# SparkFunMP3Shield.net
KiCad netlist of a schematic drawn in EAGLE
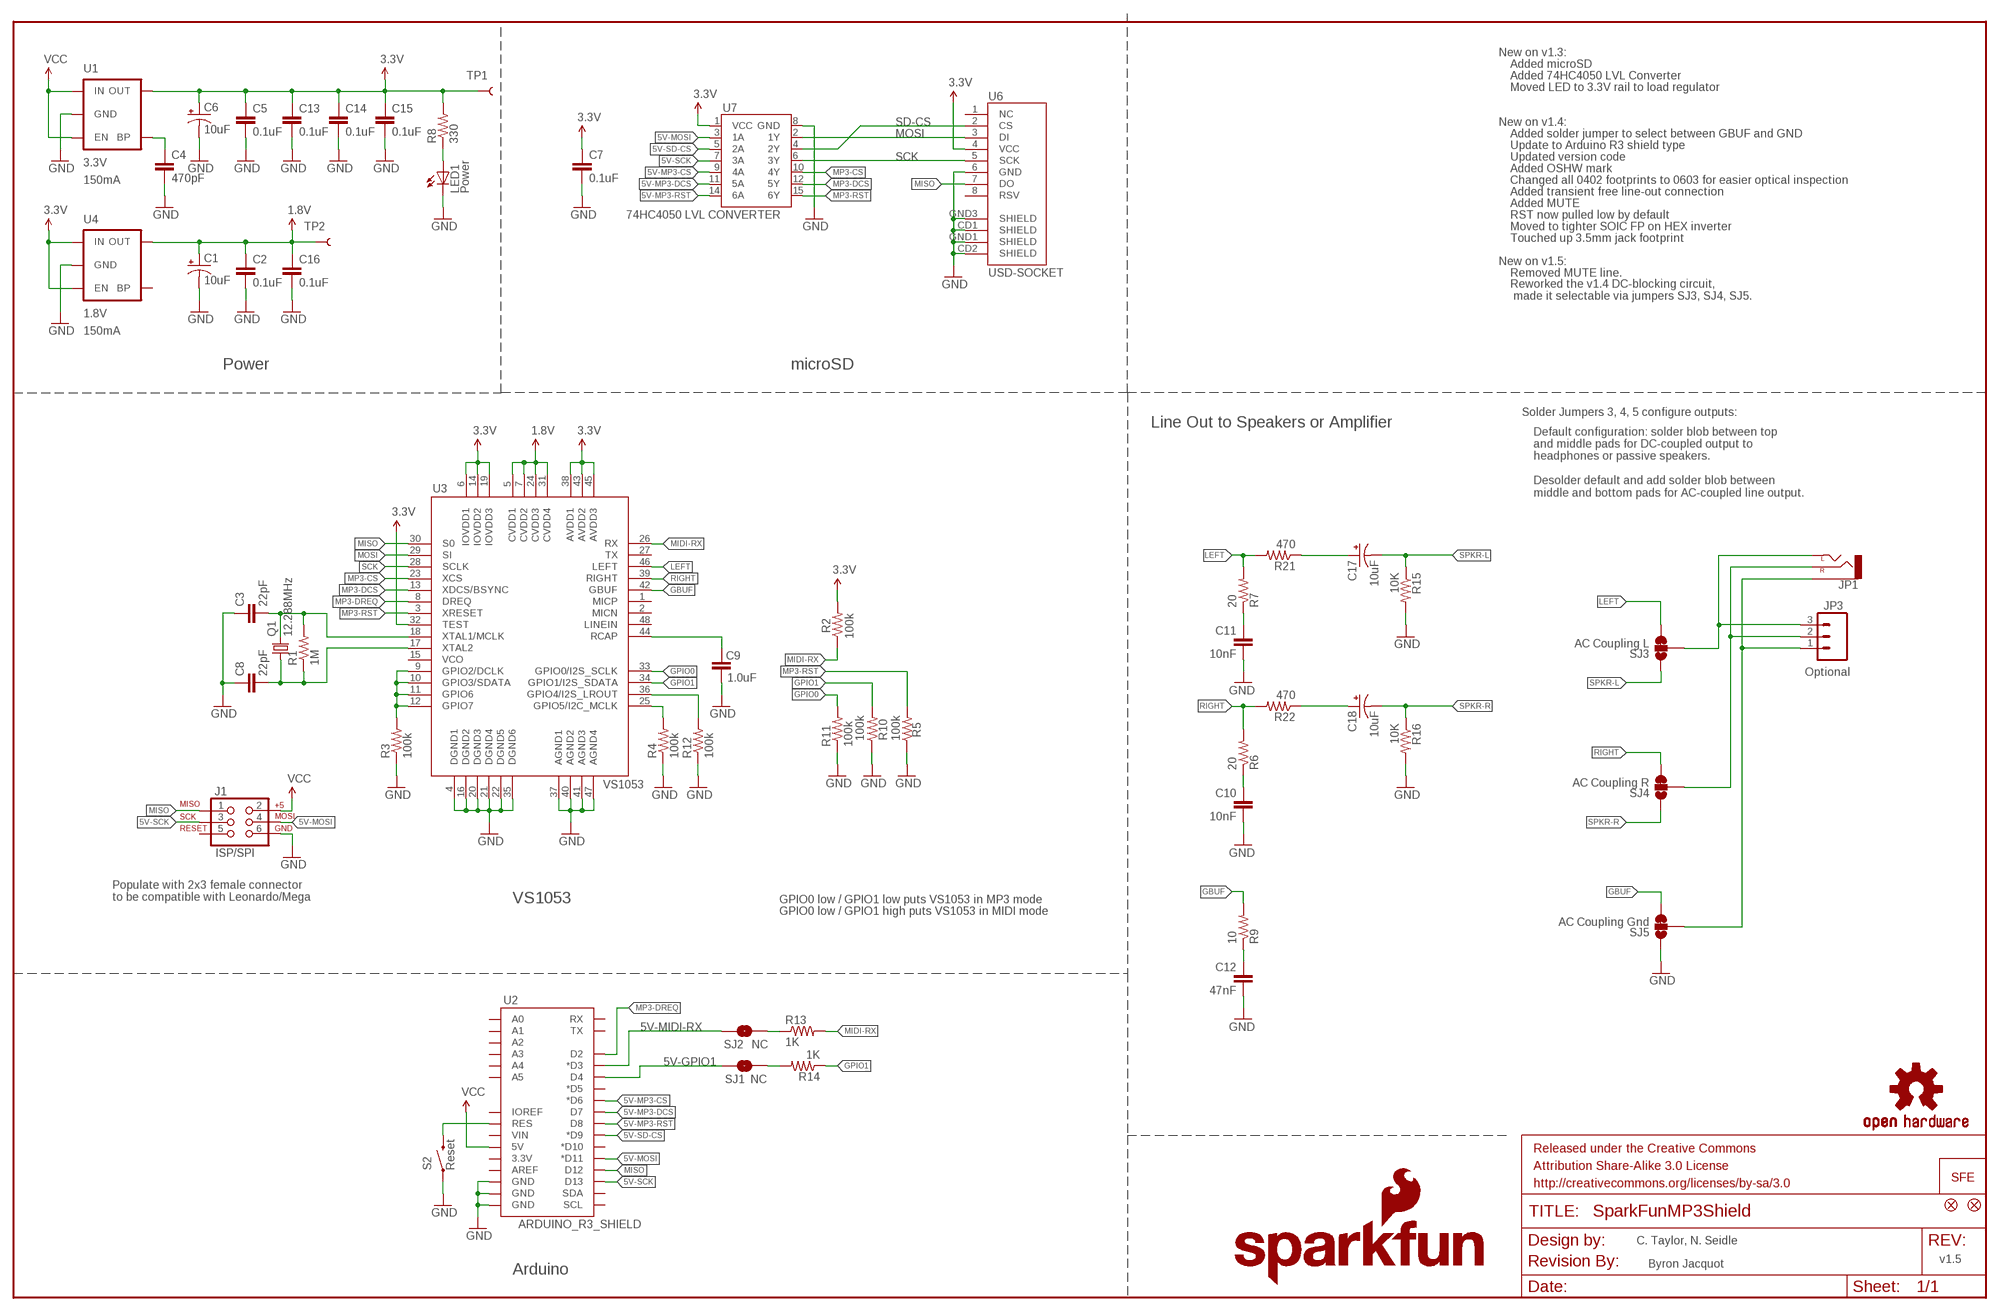
[diagram p0: schematic, sheet 1]

(export (version "E")
  (design (tool "Eeschema 10.0.6"))
  (components
    (comp (ref "C1")
      (value "10uF")
      (footprint "eagle-import:EIA3216")
      (libsource (lib "eagle-import") (part "10UF-16V-10%(TANT)"))
    )
    (comp (ref "C2")
      (value "0.1uF")
      (footprint "eagle-import:0603-CAP")
      (libsource (lib "eagle-import") (part "0.1UF-25V(+80/-20%)(0603)"))
    )
    (comp (ref "C3")
      (value "22pF")
      (footprint "eagle-import:0603-CAP")
      (libsource (lib "eagle-import") (part "22PF-50V-5%(0603)"))
    )
    (comp (ref "C4")
      (value "470pF")
      (footprint "eagle-import:0603-CAP")
      (libsource (lib "eagle-import") (part "470PF-50V-5%(0603)SMD"))
    )
    (comp (ref "C5")
      (value "0.1uF")
      (footprint "eagle-import:0603-CAP")
      (libsource (lib "eagle-import") (part "0.1UF-25V(+80/-20%)(0603)"))
    )
    (comp (ref "C6")
      (value "10uF")
      (footprint "eagle-import:EIA3216")
      (libsource (lib "eagle-import") (part "10UF-16V-10%(TANT)"))
    )
    (comp (ref "C7")
      (value "0.1uF")
      (footprint "eagle-import:0603-CAP")
      (libsource (lib "eagle-import") (part "0.1UF-25V(+80/-20%)(0603)"))
    )
    (comp (ref "C8")
      (value "22pF")
      (footprint "eagle-import:0603-CAP")
      (libsource (lib "eagle-import") (part "22PF-50V-5%(0603)"))
    )
    (comp (ref "C9")
      (value "1.0uF")
      (footprint "eagle-import:0603-CAP")
      (libsource (lib "eagle-import") (part "1.0UF-16V-10%(0603)"))
    )
    (comp (ref "C10")
      (value "10nF")
      (footprint "eagle-import:0603-CAP")
      (libsource (lib "eagle-import") (part "10NF/10000PF-50V-10%(0603)"))
    )
    (comp (ref "C11")
      (value "10nF")
      (footprint "eagle-import:0603-CAP")
      (libsource (lib "eagle-import") (part "10NF/10000PF-50V-10%(0603)"))
    )
    (comp (ref "C12")
      (value "47nF")
      (footprint "eagle-import:0603-CAP")
      (libsource (lib "eagle-import") (part "47NF(0.047UF/47000PF)-25V-5%(0603)SMD"))
    )
    (comp (ref "C13")
      (value "0.1uF")
      (footprint "eagle-import:0603-CAP")
      (libsource (lib "eagle-import") (part "0.1UF-25V(+80/-20%)(0603)"))
    )
    (comp (ref "C14")
      (value "0.1uF")
      (footprint "eagle-import:0603-CAP")
      (libsource (lib "eagle-import") (part "0.1UF-25V(+80/-20%)(0603)"))
    )
    (comp (ref "C15")
      (value "0.1uF")
      (footprint "eagle-import:0603-CAP")
      (libsource (lib "eagle-import") (part "0.1UF-25V(+80/-20%)(0603)"))
    )
    (comp (ref "C16")
      (value "0.1uF")
      (footprint "eagle-import:0603-CAP")
      (libsource (lib "eagle-import") (part "0.1UF-25V(+80/-20%)(0603)"))
    )
    (comp (ref "C17")
      (value "10uF")
      (footprint "eagle-import:EIA3216")
      (libsource (lib "eagle-import") (part "10UF-16V-10%(TANT)"))
    )
    (comp (ref "C18")
      (value "10uF")
      (footprint "eagle-import:EIA3216")
      (libsource (lib "eagle-import") (part "10UF-16V-10%(TANT)"))
    )
    (comp (ref "FRAME1")
      (value "FRAME-LEDGER")
      (footprint "eagle-import:CREATIVE_COMMONS")
      (libsource (lib "eagle-import") (part "FRAME-LEDGER"))
    )
    (comp (ref "J1")
      (value "ISP/SPI")
      (footprint "eagle-import:2X3")
      (libsource (lib "eagle-import") (part "AVR_SPI_PRG_6PTH"))
    )
    (comp (ref "JP1")
      (value "AUDIO-JACKSMD2")
      (footprint "eagle-import:AUDIO-JACK-3.5MM-SMD")
      (libsource (lib "eagle-import") (part "AUDIO-JACKSMD2"))
    )
    (comp (ref "JP3")
      (value "Optional")
      (footprint "eagle-import:1X03")
      (libsource (lib "eagle-import") (part "M03PTH"))
    )
    (comp (ref "LED1")
      (value "Power")
      (footprint "eagle-import:LED-0603")
      (libsource (lib "eagle-import") (part "LED-RED0603"))
    )
    (comp (ref "LOGO1")
      (value "OSHW-LOGOS")
      (footprint "eagle-import:OSHW-LOGO-S")
      (libsource (lib "eagle-import") (part "OSHW-LOGOS"))
    )
    (comp (ref "LOGO2")
      (value "SFE_LOGO_NAME_FLAME.1_INCH")
      (footprint "eagle-import:SFE_LOGO_NAME_FLAME_.1")
      (libsource (lib "eagle-import") (part "SFE_LOGO_NAME_FLAME.1_INCH"))
    )
    (comp (ref "Q1")
      (value "12.288MHz")
      (footprint "eagle-import:CRYSTAL-SMD-5X3")
      (libsource (lib "eagle-import") (part "CRYSTAL5X3"))
    )
    (comp (ref "R1")
      (value "1M")
      (footprint "eagle-import:0603-RES")
      (libsource (lib "eagle-import") (part "1M-1%"))
    )
    (comp (ref "R2")
      (value "100k")
      (footprint "eagle-import:0603-RES")
      (libsource (lib "eagle-import") (part "100KOHM1/10W1%(0603)"))
    )
    (comp (ref "R3")
      (value "100k")
      (footprint "eagle-import:0603-RES")
      (libsource (lib "eagle-import") (part "100KOHM1/10W1%(0603)"))
    )
    (comp (ref "R4")
      (value "100k")
      (footprint "eagle-import:0603-RES")
      (libsource (lib "eagle-import") (part "100KOHM1/10W1%(0603)"))
    )
    (comp (ref "R5")
      (value "100k")
      (footprint "eagle-import:0603-RES")
      (libsource (lib "eagle-import") (part "100KOHM1/10W1%(0603)"))
    )
    (comp (ref "R6")
      (value "20")
      (footprint "eagle-import:0603-RES")
      (libsource (lib "eagle-import") (part "20OHM1/10W1%(0603)SMD"))
    )
    (comp (ref "R7")
      (value "20")
      (footprint "eagle-import:0603-RES")
      (libsource (lib "eagle-import") (part "20OHM1/10W1%(0603)SMD"))
    )
    (comp (ref "R8")
      (value "330")
      (footprint "eagle-import:0603-RES")
      (libsource (lib "eagle-import") (part "330OHM1/10W1%(0603)"))
    )
    (comp (ref "R9")
      (value "10")
      (footprint "eagle-import:0603-RES")
      (libsource (lib "eagle-import") (part "10OHM1/10W5%0603SMD"))
    )
    (comp (ref "R10")
      (value "100k")
      (footprint "eagle-import:0603-RES")
      (libsource (lib "eagle-import") (part "100KOHM1/10W1%(0603)"))
    )
    (comp (ref "R11")
      (value "100k")
      (footprint "eagle-import:0603-RES")
      (libsource (lib "eagle-import") (part "100KOHM1/10W1%(0603)"))
    )
    (comp (ref "R12")
      (value "100k")
      (footprint "eagle-import:0603-RES")
      (libsource (lib "eagle-import") (part "100KOHM1/10W1%(0603)"))
    )
    (comp (ref "R13")
      (value "1K")
      (footprint "eagle-import:0603-RES")
      (libsource (lib "eagle-import") (part "1KOHM1/10W1%(0603)"))
    )
    (comp (ref "R14")
      (value "1K")
      (footprint "eagle-import:0603-RES")
      (libsource (lib "eagle-import") (part "1KOHM1/10W1%(0603)"))
    )
    (comp (ref "R15")
      (value "10K")
      (footprint "eagle-import:0603-RES")
      (libsource (lib "eagle-import") (part "10KOHM1/10W1%(0603)0603"))
    )
    (comp (ref "R16")
      (value "10K")
      (footprint "eagle-import:0603-RES")
      (libsource (lib "eagle-import") (part "10KOHM1/10W1%(0603)0603"))
    )
    (comp (ref "R21")
      (value "470")
      (footprint "eagle-import:0603-RES")
      (libsource (lib "eagle-import") (part "470OHM1/10W1%(0603)"))
    )
    (comp (ref "R22")
      (value "470")
      (footprint "eagle-import:0603-RES")
      (libsource (lib "eagle-import") (part "470OHM1/10W1%(0603)"))
    )
    (comp (ref "S2")
      (value "Reset")
      (footprint "eagle-import:TACTILE_SWITCH_SMD")
      (libsource (lib "eagle-import") (part "SWITCH-MOMENTARY-2SMD"))
    )
    (comp (ref "SJ1")
      (value "NC")
      (footprint "eagle-import:SJ_2S-TRACE")
      (libsource (lib "eagle-import") (part "SOLDERJUMPERTRACE"))
    )
    (comp (ref "SJ2")
      (value "NC")
      (footprint "eagle-import:SJ_2S-TRACE")
      (libsource (lib "eagle-import") (part "SOLDERJUMPERTRACE"))
    )
    (comp (ref "SJ3")
      (value "AC Coupling L")
      (footprint "eagle-import:SMT-JUMPER_3_1-NC_TRACE_SILK")
      (libsource (lib "eagle-import") (part "JUMPER-SMT_3_1-NC_TRACE_SILK"))
    )
    (comp (ref "SJ4")
      (value "AC Coupling R")
      (footprint "eagle-import:SMT-JUMPER_3_1-NC_TRACE_SILK")
      (libsource (lib "eagle-import") (part "JUMPER-SMT_3_1-NC_TRACE_SILK"))
    )
    (comp (ref "SJ5")
      (value "AC Coupling Gnd")
      (footprint "eagle-import:SMT-JUMPER_3_1-NC_TRACE_SILK")
      (libsource (lib "eagle-import") (part "JUMPER-SMT_3_1-NC_TRACE_SILK"))
    )
    (comp (ref "TP1")
      (value "TEST-POINT3X5")
      (footprint "eagle-import:PAD.03X.05")
      (libsource (lib "eagle-import") (part "TEST-POINT3X5"))
    )
    (comp (ref "TP2")
      (value "TEST-POINT3X5")
      (footprint "eagle-import:PAD.03X.05")
      (libsource (lib "eagle-import") (part "TEST-POINT3X5"))
    )
    (comp (ref "U$1")
      (value "REVISION")
      (footprint "eagle-import:REVISION")
      (libsource (lib "eagle-import") (part "REVISION"))
    )
    (comp (ref "U$4")
      (value "FIDUCIAL1X2")
      (footprint "eagle-import:FIDUCIAL-1X2")
      (libsource (lib "eagle-import") (part "FIDUCIAL1X2"))
    )
    (comp (ref "U$5")
      (value "FIDUCIAL1X2")
      (footprint "eagle-import:FIDUCIAL-1X2")
      (libsource (lib "eagle-import") (part "FIDUCIAL1X2"))
    )
    (comp (ref "U$8")
      (value "LOGO-SFENEW")
      (footprint "eagle-import:SFE-NEW-WEBLOGO")
      (libsource (lib "eagle-import") (part "LOGO-SFENEW"))
    )
    (comp (ref "U1")
      (value "3.3V")
      (footprint "eagle-import:SOT23-5")
      (libsource (lib "eagle-import") (part "V_REG_MIC52053.3V"))
    )
    (comp (ref "U2")
      (value "ARDUINO_R3_SHIELD")
      (footprint "eagle-import:UNO_R3_SHIELD")
      (libsource (lib "eagle-import") (part "ARDUINO_R3_SHIELD"))
    )
    (comp (ref "U3")
      (value "VS1053")
      (footprint "eagle-import:LQFP-48")
      (libsource (lib "eagle-import") (part "VS1033/1053SMD"))
    )
    (comp (ref "U4")
      (value "1.8V")
      (footprint "eagle-import:SC70")
      (libsource (lib "eagle-import") (part "V_REG_SP62141.8V"))
    )
    (comp (ref "U6")
      (value "USD-SOCKET")
      (footprint "eagle-import:MICRO-SD-SOCKET-PP")
      (libsource (lib "eagle-import") (part "USD-SOCKETNEW"))
    )
    (comp (ref "U7")
      (value "74HC4050 LVL CONVERTER")
      (footprint "eagle-import:SO016")
      (libsource (lib "eagle-import") (part "HEX_CONVERTER"))
    )
  )
  (nets
    (net (code "1") (name "/5V-GPIO1") (class "Default")
      (node (ref "SJ1") (pin "2") (pinfunction "2_2") (pintype "passive"))
      (node (ref "U2") (pin "D4") (pinfunction "D4_D4") (pintype "bidirectional"))
    )
    (net (code "2") (name "/5V-MIDI-RX") (class "Default")
      (node (ref "SJ2") (pin "1") (pinfunction "1_1") (pintype "passive"))
      (node (ref "U2") (pin "D3") (pinfunction "*D3_D3") (pintype "bidirectional"))
    )
    (net (code "3") (name "/SD-CS") (class "Default")
      (node (ref "U6") (pin "2") (pinfunction "CS_2") (pintype "bidirectional"))
      (node (ref "U7") (pin "4") (pinfunction "2Y_4") (pintype "bidirectional"))
    )
    (net (code "4") (name "1.8V") (class "Default")
      (node (ref "C1") (pin "A") (pinfunction "+_A") (pintype "passive"))
      (node (ref "C16") (pin "1") (pinfunction "1_1") (pintype "passive"))
      (node (ref "C2") (pin "1") (pinfunction "1_1") (pintype "passive"))
      (node (ref "TP2") (pin "P$1") (pinfunction "1_P$1") (pintype "bidirectional"))
      (node (ref "U3") (pin "24") (pinfunction "CVDD3_24") (pintype "bidirectional"))
      (node (ref "U3") (pin "31") (pinfunction "CVDD4_31") (pintype "bidirectional"))
      (node (ref "U3") (pin "5") (pinfunction "CVDD1_5") (pintype "bidirectional"))
      (node (ref "U3") (pin "7") (pinfunction "CVDD2_7") (pintype "bidirectional"))
      (node (ref "U4") (pin "5") (pinfunction "OUT_5") (pintype "passive"))
    )
    (net (code "5") (name "3.3V") (class "Default")
      (node (ref "C13") (pin "1") (pinfunction "1_1") (pintype "passive"))
      (node (ref "C14") (pin "1") (pinfunction "1_1") (pintype "passive"))
      (node (ref "C15") (pin "1") (pinfunction "1_1") (pintype "passive"))
      (node (ref "C5") (pin "1") (pinfunction "1_1") (pintype "passive"))
      (node (ref "C6") (pin "A") (pinfunction "+_A") (pintype "passive"))
      (node (ref "C7") (pin "1") (pinfunction "1_1") (pintype "passive"))
      (node (ref "R2") (pin "2") (pinfunction "2_2") (pintype "passive"))
      (node (ref "R8") (pin "2") (pinfunction "2_2") (pintype "passive"))
      (node (ref "TP1") (pin "P$1") (pinfunction "1_P$1") (pintype "bidirectional"))
      (node (ref "U1") (pin "5") (pinfunction "OUT_5") (pintype "passive"))
      (node (ref "U3") (pin "14") (pinfunction "IOVDD2_14") (pintype "bidirectional"))
      (node (ref "U3") (pin "19") (pinfunction "IOVDD3_19") (pintype "bidirectional"))
      (node (ref "U3") (pin "32") (pinfunction "TEST_32") (pintype "bidirectional"))
      (node (ref "U3") (pin "38") (pinfunction "AVDD1_38") (pintype "bidirectional"))
      (node (ref "U3") (pin "43") (pinfunction "AVDD2_43") (pintype "bidirectional"))
      (node (ref "U3") (pin "45") (pinfunction "AVDD3_45") (pintype "bidirectional"))
      (node (ref "U3") (pin "6") (pinfunction "IOVDD1_6") (pintype "bidirectional"))
      (node (ref "U4") (pin "1") (pinfunction "IN_1") (pintype "input"))
      (node (ref "U4") (pin "3") (pinfunction "EN_3") (pintype "input"))
      (node (ref "U6") (pin "4") (pinfunction "VCC_4") (pintype "bidirectional"))
      (node (ref "U7") (pin "1") (pinfunction "VCC_1") (pintype "bidirectional"))
    )
    (net (code "6") (name "5V-MOSI") (class "Default")
      (node (ref "J1") (pin "4") (pinfunction "4_4") (pintype "passive"))
      (node (ref "U2") (pin "D11") (pinfunction "*D11_D11") (pintype "bidirectional"))
      (node (ref "U7") (pin "3") (pinfunction "1A_3") (pintype "bidirectional"))
    )
    (net (code "7") (name "5V-MP3-CS") (class "Default")
      (node (ref "U2") (pin "D6") (pinfunction "*D6_D6") (pintype "bidirectional"))
      (node (ref "U7") (pin "9") (pinfunction "4A_9") (pintype "bidirectional"))
    )
    (net (code "8") (name "5V-MP3-DCS") (class "Default")
      (node (ref "U2") (pin "D7") (pinfunction "D7_D7") (pintype "bidirectional"))
      (node (ref "U7") (pin "11") (pinfunction "5A_11") (pintype "bidirectional"))
    )
    (net (code "9") (name "5V-MP3-RST") (class "Default")
      (node (ref "U2") (pin "D8") (pinfunction "D8_D8") (pintype "bidirectional"))
      (node (ref "U7") (pin "14") (pinfunction "6A_14") (pintype "bidirectional"))
    )
    (net (code "10") (name "5V-SCK") (class "Default")
      (node (ref "J1") (pin "3") (pinfunction "3_3") (pintype "passive"))
      (node (ref "U2") (pin "D13") (pinfunction "D13_D13") (pintype "bidirectional"))
      (node (ref "U7") (pin "7") (pinfunction "3A_7") (pintype "bidirectional"))
    )
    (net (code "11") (name "5V-SD-CS") (class "Default")
      (node (ref "U2") (pin "D9") (pinfunction "*D9_D9") (pintype "bidirectional"))
      (node (ref "U7") (pin "5") (pinfunction "2A_5") (pintype "bidirectional"))
    )
    (net (code "12") (name "GBUF") (class "Default")
      (node (ref "R9") (pin "2") (pinfunction "2_2") (pintype "passive"))
      (node (ref "SJ5") (pin "3") (pinfunction "3_3") (pintype "passive"))
      (node (ref "U3") (pin "42") (pinfunction "GBUF_42") (pintype "bidirectional"))
    )
    (net (code "13") (name "GND") (class "Default")
      (node (ref "C1") (pin "C") (pinfunction "-_C") (pintype "passive"))
      (node (ref "C10") (pin "2") (pinfunction "2_2") (pintype "passive"))
      (node (ref "C11") (pin "2") (pinfunction "2_2") (pintype "passive"))
      (node (ref "C12") (pin "2") (pinfunction "2_2") (pintype "passive"))
      (node (ref "C13") (pin "2") (pinfunction "2_2") (pintype "passive"))
      (node (ref "C14") (pin "2") (pinfunction "2_2") (pintype "passive"))
      (node (ref "C15") (pin "2") (pinfunction "2_2") (pintype "passive"))
      (node (ref "C16") (pin "2") (pinfunction "2_2") (pintype "passive"))
      (node (ref "C2") (pin "2") (pinfunction "2_2") (pintype "passive"))
      (node (ref "C3") (pin "1") (pinfunction "1_1") (pintype "passive"))
      (node (ref "C4") (pin "2") (pinfunction "2_2") (pintype "passive"))
      (node (ref "C5") (pin "2") (pinfunction "2_2") (pintype "passive"))
      (node (ref "C6") (pin "C") (pinfunction "-_C") (pintype "passive"))
      (node (ref "C7") (pin "2") (pinfunction "2_2") (pintype "passive"))
      (node (ref "C8") (pin "1") (pinfunction "1_1") (pintype "passive"))
      (node (ref "C9") (pin "1") (pinfunction "1_1") (pintype "passive"))
      (node (ref "J1") (pin "6") (pinfunction "6_6") (pintype "passive"))
      (node (ref "LED1") (pin "C") (pinfunction "C_C") (pintype "passive"))
      (node (ref "R10") (pin "1") (pinfunction "1_1") (pintype "passive"))
      (node (ref "R11") (pin "1") (pinfunction "1_1") (pintype "passive"))
      (node (ref "R12") (pin "1") (pinfunction "1_1") (pintype "passive"))
      (node (ref "R15") (pin "2") (pinfunction "2_2") (pintype "passive"))
      (node (ref "R16") (pin "2") (pinfunction "2_2") (pintype "passive"))
      (node (ref "R3") (pin "1") (pinfunction "1_1") (pintype "passive"))
      (node (ref "R4") (pin "1") (pinfunction "1_1") (pintype "passive"))
      (node (ref "R5") (pin "1") (pinfunction "1_1") (pintype "passive"))
      (node (ref "S2") (pin "1") (pinfunction "1_1") (pintype "passive"))
      (node (ref "SJ5") (pin "1") (pinfunction "1_1") (pintype "passive"))
      (node (ref "U1") (pin "2") (pinfunction "GND_2") (pintype "input"))
      (node (ref "U2") (pin "GND@0") (pinfunction "GND_GND@0") (pintype "bidirectional"))
      (node (ref "U2") (pin "GND@1") (pinfunction "GND_GND@1") (pintype "bidirectional"))
      (node (ref "U2") (pin "GND@2") (pinfunction "GND_GND@2") (pintype "bidirectional"))
      (node (ref "U3") (pin "16") (pinfunction "DGND2_16") (pintype "bidirectional"))
      (node (ref "U3") (pin "20") (pinfunction "DGND3_20") (pintype "bidirectional"))
      (node (ref "U3") (pin "21") (pinfunction "DGND4_21") (pintype "bidirectional"))
      (node (ref "U3") (pin "22") (pinfunction "DGND5_22") (pintype "bidirectional"))
      (node (ref "U3") (pin "35") (pinfunction "DGND6_35") (pintype "bidirectional"))
      (node (ref "U3") (pin "37") (pinfunction "AGND1_37") (pintype "bidirectional"))
      (node (ref "U3") (pin "4") (pinfunction "DGND1_4") (pintype "bidirectional"))
      (node (ref "U3") (pin "40") (pinfunction "AGND2_40") (pintype "bidirectional"))
      (node (ref "U3") (pin "41") (pinfunction "AGND3_41") (pintype "bidirectional"))
      (node (ref "U3") (pin "47") (pinfunction "AGND4_47") (pintype "bidirectional"))
      (node (ref "U4") (pin "2") (pinfunction "GND_2") (pintype "input"))
      (node (ref "U6") (pin "6") (pinfunction "GND_6") (pintype "bidirectional"))
      (node (ref "U6") (pin "CD1") (pinfunction "SHIELD_CD1") (pintype "bidirectional"))
      (node (ref "U6") (pin "CD2") (pinfunction "SHIELD_CD2") (pintype "bidirectional"))
      (node (ref "U6") (pin "GND1") (pinfunction "SHIELD_GND1") (pintype "bidirectional"))
      (node (ref "U6") (pin "GND3") (pinfunction "SHIELD_GND3") (pintype "bidirectional"))
      (node (ref "U7") (pin "8") (pinfunction "GND_8") (pintype "bidirectional"))
    )
    (net (code "14") (name "GPIO0") (class "Default")
      (node (ref "R11") (pin "2") (pinfunction "2_2") (pintype "passive"))
      (node (ref "U3") (pin "33") (pinfunction "GPIO0/I2S_SCLK_33") (pintype "bidirectional"))
    )
    (net (code "15") (name "GPIO1") (class "Default")
      (node (ref "R10") (pin "2") (pinfunction "2_2") (pintype "passive"))
      (node (ref "R14") (pin "1") (pinfunction "1_1") (pintype "passive"))
      (node (ref "U3") (pin "34") (pinfunction "GPIO1/I2S_SDATA_34") (pintype "bidirectional"))
    )
    (net (code "16") (name "LEFT") (class "Default")
      (node (ref "R21") (pin "2") (pinfunction "2_2") (pintype "passive"))
      (node (ref "R7") (pin "2") (pinfunction "2_2") (pintype "passive"))
      (node (ref "SJ3") (pin "3") (pinfunction "3_3") (pintype "passive"))
      (node (ref "U3") (pin "46") (pinfunction "LEFT_46") (pintype "bidirectional"))
    )
    (net (code "17") (name "MIDI-RX") (class "Default")
      (node (ref "R13") (pin "2") (pinfunction "2_2") (pintype "passive"))
      (node (ref "R2") (pin "1") (pinfunction "1_1") (pintype "passive"))
      (node (ref "U3") (pin "26") (pinfunction "RX_26") (pintype "bidirectional"))
    )
    (net (code "18") (name "MISO") (class "Default")
      (node (ref "J1") (pin "1") (pinfunction "1_1") (pintype "passive"))
      (node (ref "U2") (pin "D12") (pinfunction "D12_D12") (pintype "bidirectional"))
      (node (ref "U3") (pin "30") (pinfunction "S0_30") (pintype "bidirectional"))
      (node (ref "U6") (pin "7") (pinfunction "DO_7") (pintype "bidirectional"))
    )
    (net (code "19") (name "MOSI") (class "Default")
      (node (ref "U3") (pin "29") (pinfunction "SI_29") (pintype "bidirectional"))
      (node (ref "U6") (pin "3") (pinfunction "DI_3") (pintype "bidirectional"))
      (node (ref "U7") (pin "2") (pinfunction "1Y_2") (pintype "bidirectional"))
    )
    (net (code "20") (name "MP3-CS") (class "Default")
      (node (ref "U3") (pin "23") (pinfunction "XCS_23") (pintype "bidirectional"))
      (node (ref "U7") (pin "10") (pinfunction "4Y_10") (pintype "bidirectional"))
    )
    (net (code "21") (name "MP3-DCS") (class "Default")
      (node (ref "U3") (pin "13") (pinfunction "XDCS/BSYNC_13") (pintype "bidirectional"))
      (node (ref "U7") (pin "12") (pinfunction "5Y_12") (pintype "bidirectional"))
    )
    (net (code "22") (name "MP3-DREQ") (class "Default")
      (node (ref "U2") (pin "D2") (pinfunction "D2_D2") (pintype "bidirectional"))
      (node (ref "U3") (pin "8") (pinfunction "DREQ_8") (pintype "bidirectional"))
    )
    (net (code "23") (name "MP3-RST") (class "Default")
      (node (ref "R5") (pin "2") (pinfunction "2_2") (pintype "passive"))
      (node (ref "U3") (pin "3") (pinfunction "XRESET_3") (pintype "bidirectional"))
      (node (ref "U7") (pin "15") (pinfunction "6Y_15") (pintype "bidirectional"))
    )
    (net (code "24") (name "Net-(C10-Pad1)") (class "Default")
      (node (ref "C10") (pin "1") (pinfunction "1_1") (pintype "passive"))
      (node (ref "R6") (pin "1") (pinfunction "1_1") (pintype "passive"))
    )
    (net (code "25") (name "Net-(C11-Pad1)") (class "Default")
      (node (ref "C11") (pin "1") (pinfunction "1_1") (pintype "passive"))
      (node (ref "R7") (pin "1") (pinfunction "1_1") (pintype "passive"))
    )
    (net (code "26") (name "Net-(C12-Pad1)") (class "Default")
      (node (ref "C12") (pin "1") (pinfunction "1_1") (pintype "passive"))
      (node (ref "R9") (pin "1") (pinfunction "1_1") (pintype "passive"))
    )
    (net (code "27") (name "Net-(C17-+)") (class "Default")
      (node (ref "C17") (pin "A") (pinfunction "+_A") (pintype "passive"))
      (node (ref "R21") (pin "1") (pinfunction "1_1") (pintype "passive"))
    )
    (net (code "28") (name "Net-(C18-+)") (class "Default")
      (node (ref "C18") (pin "A") (pinfunction "+_A") (pintype "passive"))
      (node (ref "R22") (pin "1") (pinfunction "1_1") (pintype "passive"))
    )
    (net (code "29") (name "Net-(JP1-LEFT)") (class "Default")
      (node (ref "JP1") (pin "TIP") (pinfunction "LEFT_TIP") (pintype "bidirectional"))
      (node (ref "JP3") (pin "3") (pinfunction "3_3") (pintype "passive"))
      (node (ref "SJ3") (pin "2") (pinfunction "2_2") (pintype "passive"))
    )
    (net (code "30") (name "Net-(JP1-PadSLEEVE)") (class "Default")
      (node (ref "JP1") (pin "SLEEVE") (pinfunction "SLEEVE_SLEEVE") (pintype "bidirectional"))
      (node (ref "JP3") (pin "1") (pinfunction "1_1") (pintype "passive"))
      (node (ref "SJ5") (pin "2") (pinfunction "2_2") (pintype "passive"))
    )
    (net (code "31") (name "Net-(JP1-RIGHT)") (class "Default")
      (node (ref "JP1") (pin "RING") (pinfunction "RIGHT_RING") (pintype "bidirectional"))
      (node (ref "JP3") (pin "2") (pinfunction "2_2") (pintype "passive"))
      (node (ref "SJ4") (pin "2") (pinfunction "2_2") (pintype "passive"))
    )
    (net (code "32") (name "Net-(LED1-PadA)") (class "Default")
      (node (ref "LED1") (pin "A") (pinfunction "A_A") (pintype "passive"))
      (node (ref "R8") (pin "1") (pinfunction "1_1") (pintype "passive"))
    )
    (net (code "33") (name "Net-(Q1-2)") (class "Default")
      (node (ref "C3") (pin "2") (pinfunction "2_2") (pintype "passive"))
      (node (ref "Q1") (pin "3") (pinfunction "2_3") (pintype "passive"))
      (node (ref "R1") (pin "2") (pinfunction "2_2") (pintype "passive"))
      (node (ref "U3") (pin "18") (pinfunction "XTAL1/MCLK_18") (pintype "bidirectional"))
    )
    (net (code "34") (name "Net-(R13-Pad1)") (class "Default")
      (node (ref "R13") (pin "1") (pinfunction "1_1") (pintype "passive"))
      (node (ref "SJ2") (pin "2") (pinfunction "2_2") (pintype "passive"))
    )
    (net (code "35") (name "Net-(R14-Pad2)") (class "Default")
      (node (ref "R14") (pin "2") (pinfunction "2_2") (pintype "passive"))
      (node (ref "SJ1") (pin "1") (pinfunction "1_1") (pintype "passive"))
    )
    (net (code "36") (name "Net-(S2-2)") (class "Default")
      (node (ref "S2") (pin "3") (pinfunction "2_3") (pintype "passive"))
      (node (ref "U2") (pin "RES") (pinfunction "RES_RES") (pintype "bidirectional"))
    )
    (net (code "37") (name "Net-(U1-BP)") (class "Default")
      (node (ref "C4") (pin "1") (pinfunction "1_1") (pintype "passive"))
      (node (ref "U1") (pin "4") (pinfunction "BP_4") (pintype "input"))
    )
    (net (code "38") (name "Net-(U3-GPIO2{slash}DCLK)") (class "Default")
      (node (ref "R3") (pin "2") (pinfunction "2_2") (pintype "passive"))
      (node (ref "U3") (pin "10") (pinfunction "GPIO3/SDATA_10") (pintype "bidirectional"))
      (node (ref "U3") (pin "11") (pinfunction "GPIO6_11") (pintype "bidirectional"))
      (node (ref "U3") (pin "12") (pinfunction "GPIO7_12") (pintype "bidirectional"))
      (node (ref "U3") (pin "9") (pinfunction "GPIO2/DCLK_9") (pintype "bidirectional"))
    )
    (net (code "39") (name "Net-(U3-GPIO4{slash}I2S_LROUT)") (class "Default")
      (node (ref "R12") (pin "2") (pinfunction "2_2") (pintype "passive"))
      (node (ref "U3") (pin "36") (pinfunction "GPIO4/I2S_LROUT_36") (pintype "bidirectional"))
    )
    (net (code "40") (name "Net-(U3-GPIO5{slash}I2C_MCLK)") (class "Default")
      (node (ref "R4") (pin "2") (pinfunction "2_2") (pintype "passive"))
      (node (ref "U3") (pin "25") (pinfunction "GPIO5/I2C_MCLK_25") (pintype "bidirectional"))
    )
    (net (code "41") (name "Net-(U3-RCAP)") (class "Default")
      (node (ref "C9") (pin "2") (pinfunction "2_2") (pintype "passive"))
      (node (ref "U3") (pin "44") (pinfunction "RCAP_44") (pintype "bidirectional"))
    )
    (net (code "42") (name "Net-(U3-XTAL2)") (class "Default")
      (node (ref "C8") (pin "2") (pinfunction "2_2") (pintype "passive"))
      (node (ref "Q1") (pin "1") (pinfunction "1_1") (pintype "passive"))
      (node (ref "R1") (pin "1") (pinfunction "1_1") (pintype "passive"))
      (node (ref "U3") (pin "17") (pinfunction "XTAL2_17") (pintype "bidirectional"))
    )
    (net (code "43") (name "RIGHT") (class "Default")
      (node (ref "R22") (pin "2") (pinfunction "2_2") (pintype "passive"))
      (node (ref "R6") (pin "2") (pinfunction "2_2") (pintype "passive"))
      (node (ref "SJ4") (pin "3") (pinfunction "3_3") (pintype "passive"))
      (node (ref "U3") (pin "39") (pinfunction "RIGHT_39") (pintype "bidirectional"))
    )
    (net (code "44") (name "SCK") (class "Default")
      (node (ref "U3") (pin "28") (pinfunction "SCLK_28") (pintype "bidirectional"))
      (node (ref "U6") (pin "5") (pinfunction "SCK_5") (pintype "bidirectional"))
      (node (ref "U7") (pin "6") (pinfunction "3Y_6") (pintype "bidirectional"))
    )
    (net (code "45") (name "SPKR-L") (class "Default")
      (node (ref "C17") (pin "C") (pinfunction "-_C") (pintype "passive"))
      (node (ref "R15") (pin "1") (pinfunction "1_1") (pintype "passive"))
      (node (ref "SJ3") (pin "1") (pinfunction "1_1") (pintype "passive"))
    )
    (net (code "46") (name "SPKR-R") (class "Default")
      (node (ref "C18") (pin "C") (pinfunction "-_C") (pintype "passive"))
      (node (ref "R16") (pin "1") (pinfunction "1_1") (pintype "passive"))
      (node (ref "SJ4") (pin "1") (pinfunction "1_1") (pintype "passive"))
    )
    (net (code "47") (name "VCC") (class "Default")
      (node (ref "J1") (pin "2") (pinfunction "2_2") (pintype "passive"))
      (node (ref "U1") (pin "1") (pinfunction "IN_1") (pintype "input"))
      (node (ref "U1") (pin "3") (pinfunction "EN_3") (pintype "input"))
      (node (ref "U2") (pin "5V") (pinfunction "5V_5V") (pintype "bidirectional"))
    )
    (net (code "48") (name "unconnected-(J1-Pad5)") (class "Default")
      (node (ref "J1") (pin "5") (pinfunction "5_5") (pintype "passive"))
    )
    (net (code "49") (name "unconnected-(U2-*D5-PadD5)") (class "Default")
      (node (ref "U2") (pin "D5") (pinfunction "*D5_D5") (pintype "bidirectional"))
    )
    (net (code "50") (name "unconnected-(U2-*D10-PadD10)") (class "Default")
      (node (ref "U2") (pin "D10") (pinfunction "*D10_D10") (pintype "bidirectional"))
    )
    (net (code "51") (name "unconnected-(U2-Pad3.3V)") (class "Default")
      (node (ref "U2") (pin "3.3V") (pinfunction "3.3V_3.3V") (pintype "bidirectional"))
    )
    (net (code "52") (name "unconnected-(U2-PadA0)") (class "Default")
      (node (ref "U2") (pin "A0") (pinfunction "A0_A0") (pintype "bidirectional"))
    )
    (net (code "53") (name "unconnected-(U2-PadA1)") (class "Default")
      (node (ref "U2") (pin "A1") (pinfunction "A1_A1") (pintype "bidirectional"))
    )
    (net (code "54") (name "unconnected-(U2-PadA2)") (class "Default")
      (node (ref "U2") (pin "A2") (pinfunction "A2_A2") (pintype "bidirectional"))
    )
    (net (code "55") (name "unconnected-(U2-PadA3)") (class "Default")
      (node (ref "U2") (pin "A3") (pinfunction "A3_A3") (pintype "bidirectional"))
    )
    (net (code "56") (name "unconnected-(U2-PadA4)") (class "Default")
      (node (ref "U2") (pin "A4") (pinfunction "A4_A4") (pintype "bidirectional"))
    )
    (net (code "57") (name "unconnected-(U2-PadA5)") (class "Default")
      (node (ref "U2") (pin "A5") (pinfunction "A5_A5") (pintype "bidirectional"))
    )
    (net (code "58") (name "unconnected-(U2-PadAREF)") (class "Default")
      (node (ref "U2") (pin "AREF") (pinfunction "AREF_AREF") (pintype "bidirectional"))
    )
    (net (code "59") (name "unconnected-(U2-PadIOREF)") (class "Default")
      (node (ref "U2") (pin "IOREF") (pinfunction "IOREF_IOREF") (pintype "bidirectional"))
    )
    (net (code "60") (name "unconnected-(U2-PadRX)") (class "Default")
      (node (ref "U2") (pin "RX") (pinfunction "RX_RX") (pintype "bidirectional"))
    )
    (net (code "61") (name "unconnected-(U2-PadSCL)") (class "Default")
      (node (ref "U2") (pin "SCL") (pinfunction "SCL_SCL") (pintype "bidirectional"))
    )
    (net (code "62") (name "unconnected-(U2-PadSDA)") (class "Default")
      (node (ref "U2") (pin "SDA") (pinfunction "SDA_SDA") (pintype "bidirectional"))
    )
    (net (code "63") (name "unconnected-(U2-PadTX)") (class "Default")
      (node (ref "U2") (pin "TX") (pinfunction "TX_TX") (pintype "bidirectional"))
    )
    (net (code "64") (name "unconnected-(U2-PadVIN)") (class "Default")
      (node (ref "U2") (pin "VIN") (pinfunction "VIN_VIN") (pintype "bidirectional"))
    )
    (net (code "65") (name "unconnected-(U3-LINEIN-Pad48)") (class "Default")
      (node (ref "U3") (pin "48") (pinfunction "LINEIN_48") (pintype "bidirectional"))
    )
    (net (code "66") (name "unconnected-(U3-MICN-Pad2)") (class "Default")
      (node (ref "U3") (pin "2") (pinfunction "MICN_2") (pintype "bidirectional"))
    )
    (net (code "67") (name "unconnected-(U3-MICP-Pad1)") (class "Default")
      (node (ref "U3") (pin "1") (pinfunction "MICP_1") (pintype "bidirectional"))
    )
    (net (code "68") (name "unconnected-(U3-TX-Pad27)") (class "Default")
      (node (ref "U3") (pin "27") (pinfunction "TX_27") (pintype "bidirectional"))
    )
    (net (code "69") (name "unconnected-(U3-VCO-Pad15)") (class "Default")
      (node (ref "U3") (pin "15") (pinfunction "VCO_15") (pintype "bidirectional"))
    )
    (net (code "70") (name "unconnected-(U4-BP-Pad4)") (class "Default")
      (node (ref "U4") (pin "4") (pinfunction "BP_4") (pintype "input"))
    )
    (net (code "71") (name "unconnected-(U6-NC-Pad1)") (class "Default")
      (node (ref "U6") (pin "1") (pinfunction "NC_1") (pintype "bidirectional"))
    )
    (net (code "72") (name "unconnected-(U6-RSV-Pad8)") (class "Default")
      (node (ref "U6") (pin "8") (pinfunction "RSV_8") (pintype "bidirectional"))
    )
  )
)
